# BRIDGE_RECTIFIER.net
KiCad netlist of a schematic drawn in Altium Designer
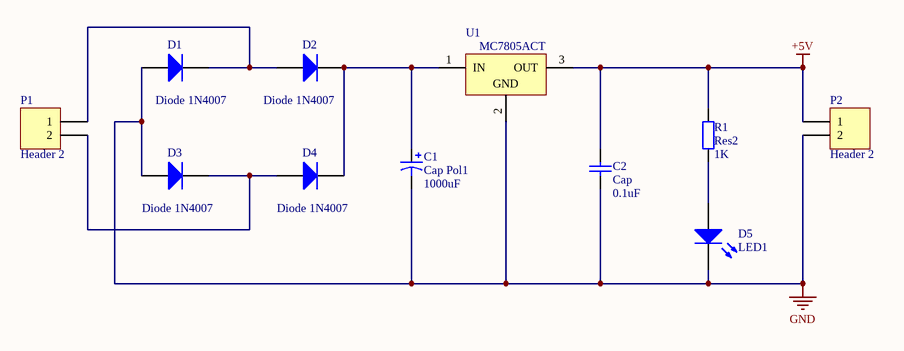
[diagram p0: BRIDGE_RECTIFIER.SchDoc]

(export (version "E")
  (design (tool "Eeschema 10.0.6"))
  (components
    (comp (ref "C1")
      (value "Cap Pol1")
      (footprint "RB7.6-15")
      (description "Polarized Capacitor (Radial)")
      (fields (field (name "ALTIUM_VALUE") "1000uF") (field (name "PUBLISHER") "Altium Limited"))
      (libsource (lib "Miscellaneous Devices") (part "Cap Pol1"))
    )
    (comp (ref "C2")
      (value "Cap")
      (footprint "RAD-0.3")
      (description "Capacitor")
      (fields (field (name "ALTIUM_VALUE") "0.1uF") (field (name "PUBLISHER") "Altium Limited"))
      (libsource (lib "Miscellaneous Devices") (part "Cap"))
    )
    (comp (ref "D1")
      (value "Diode 1N4007")
      (footprint "DIO10.46-5.3x2.8")
      (description "1 Amp General Purpose Rectifier")
      (fields (field (name "PUBLISHER") "Altium Limited"))
      (libsource (lib "Miscellaneous Devices") (part "Diode 1N4007"))
    )
    (comp (ref "D2")
      (value "Diode 1N4007")
      (footprint "DIO10.46-5.3x2.8")
      (description "1 Amp General Purpose Rectifier")
      (fields (field (name "PUBLISHER") "Altium Limited"))
      (libsource (lib "Miscellaneous Devices") (part "Diode 1N4007"))
    )
    (comp (ref "D3")
      (value "Diode 1N4007")
      (footprint "DIO10.46-5.3x2.8")
      (description "1 Amp General Purpose Rectifier")
      (fields (field (name "PUBLISHER") "Altium Limited"))
      (libsource (lib "Miscellaneous Devices") (part "Diode 1N4007"))
    )
    (comp (ref "D4")
      (value "Diode 1N4007")
      (footprint "DIO10.46-5.3x2.8")
      (description "1 Amp General Purpose Rectifier")
      (fields (field (name "PUBLISHER") "Altium Limited"))
      (libsource (lib "Miscellaneous Devices") (part "Diode 1N4007"))
    )
    (comp (ref "D5")
      (value "LED1")
      (footprint "LED-1")
      (description "Typical RED GaAs LED")
      (fields (field (name "PUBLISHER") "Altium Limited"))
      (libsource (lib "Miscellaneous Devices") (part "LED1"))
    )
    (comp (ref "P1")
      (value "Header 2")
      (footprint "HDR1X2")
      (description "Header, 2-Pin")
      (fields (field (name "PUBLISHER") "Altium Limited"))
      (libsource (lib "Miscellaneous Connectors") (part "Header 2"))
    )
    (comp (ref "P2")
      (value "Header 2")
      (footprint "HDR1X2")
      (description "Header, 2-Pin")
      (fields (field (name "PUBLISHER") "Altium Limited"))
      (libsource (lib "") (part "Header 2_1"))
    )
    (comp (ref "R1")
      (value "Res2")
      (footprint "AXIAL-0.4")
      (description "Resistor")
      (fields (field (name "ALTIUM_VALUE") "1K") (field (name "PUBLISHER") "Altium Limited"))
      (libsource (lib "Miscellaneous Devices") (part "Res2"))
    )
    (comp (ref "U1")
      (value "MC7805ACT")
      (footprint "221A-04")
      (description "3-Terminal Positive Fixed Voltage Regulator")
      (fields (field (name "PUBLISHER") "Altium Limited"))
      (libsource (lib "Motorola Power Mgt Voltage Regulator") (part "MC7805ACT"))
    )
  )
  (nets
    (net (code "1") (name "+5V") (class "Default")
      (node (ref "C2") (pin "2") (pinfunction "2_2") (pintype "passive"))
      (node (ref "P2") (pin "1") (pinfunction "1_1") (pintype "passive"))
      (node (ref "R1") (pin "2") (pinfunction "2_2") (pintype "passive"))
      (node (ref "U1") (pin "3") (pinfunction "OUT_3") (pintype "power_in"))
    )
    (net (code "2") (name "GND") (class "Default")
      (node (ref "C1") (pin "2") (pinfunction "2_2") (pintype "passive"))
      (node (ref "C2") (pin "1") (pinfunction "1_1") (pintype "passive"))
      (node (ref "D1") (pin "1") (pinfunction "A_1") (pintype "passive"))
      (node (ref "D3") (pin "1") (pinfunction "A_1") (pintype "passive"))
      (node (ref "D5") (pin "2") (pinfunction "K_2") (pintype "passive"))
      (node (ref "P2") (pin "2") (pinfunction "2_2") (pintype "passive"))
      (node (ref "U1") (pin "2") (pinfunction "GND_2") (pintype "power_in"))
    )
    (net (code "3") (name "Net-(D1-K)") (class "Default")
      (node (ref "D1") (pin "2") (pinfunction "K_2") (pintype "passive"))
      (node (ref "D2") (pin "1") (pinfunction "A_1") (pintype "passive"))
      (node (ref "P1") (pin "1") (pinfunction "1_1") (pintype "passive"))
    )
    (net (code "4") (name "Net-(D2-K)") (class "Default")
      (node (ref "C1") (pin "1") (pinfunction "1_1") (pintype "passive"))
      (node (ref "D2") (pin "2") (pinfunction "K_2") (pintype "passive"))
      (node (ref "D4") (pin "2") (pinfunction "K_2") (pintype "passive"))
      (node (ref "U1") (pin "1") (pinfunction "IN_1") (pintype "power_in"))
    )
    (net (code "5") (name "Net-(D3-K)") (class "Default")
      (node (ref "D3") (pin "2") (pinfunction "K_2") (pintype "passive"))
      (node (ref "D4") (pin "1") (pinfunction "A_1") (pintype "passive"))
      (node (ref "P1") (pin "2") (pinfunction "2_2") (pintype "passive"))
    )
    (net (code "6") (name "Net-(D5-A)") (class "Default")
      (node (ref "D5") (pin "1") (pinfunction "A_1") (pintype "passive"))
      (node (ref "R1") (pin "1") (pinfunction "1_1") (pintype "passive"))
    )
  )
)
